# rapidshark-lipo-sensor-mk-3_1.net
KiCad netlist of a schematic drawn in EAGLE
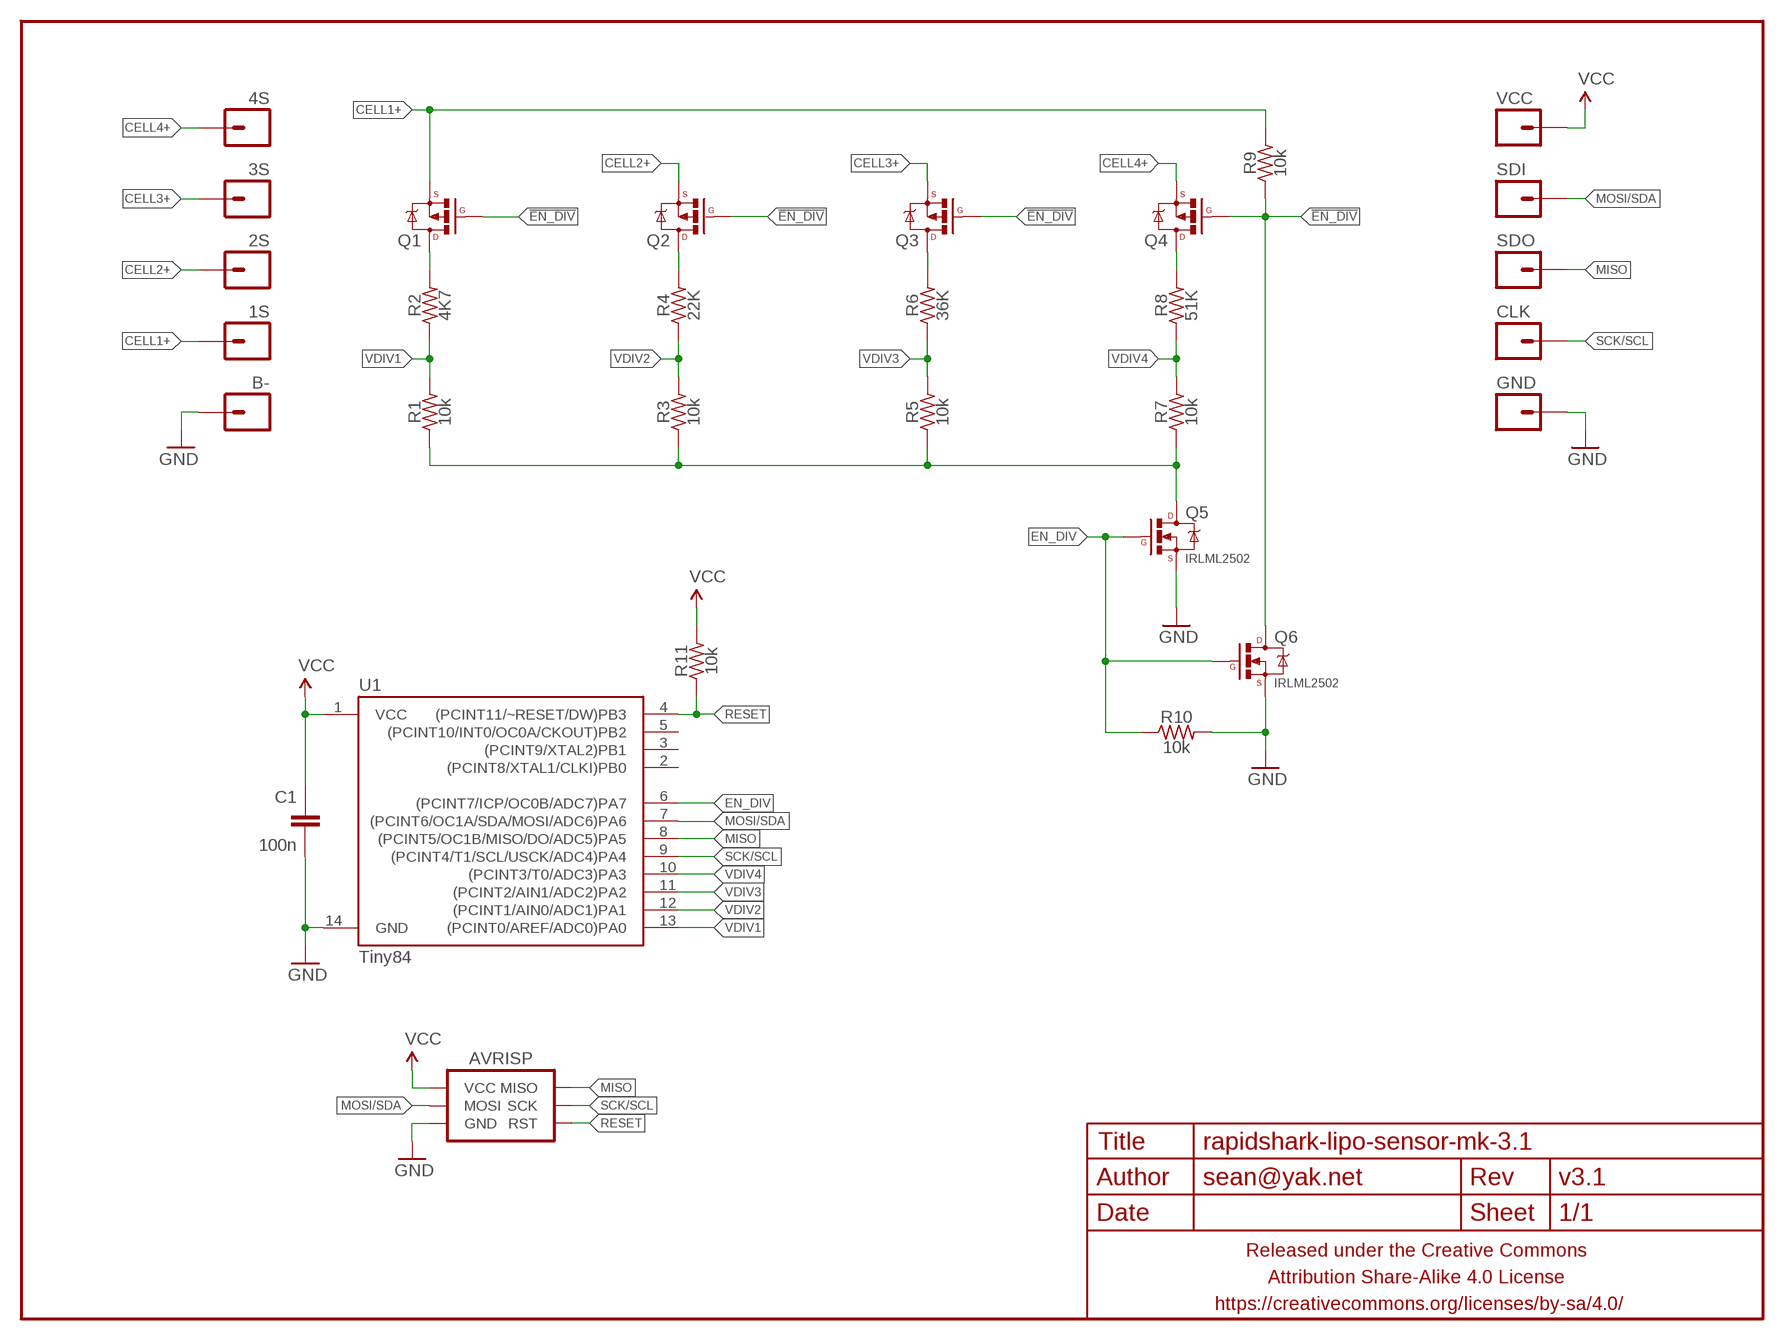
[diagram p0: schematic, sheet 1]

(export (version "E")
  (design (tool "Eeschema 10.0.6"))
  (components
    (comp (ref "1S")
      (value "M01PTH-0.9MM")
      (footprint "eagle-import:1X01-0.9MM")
      (libsource (lib "eagle-import") (part "M01PTH-0.9MM"))
    )
    (comp (ref "2S")
      (value "M01PTH-0.9MM")
      (footprint "eagle-import:1X01-0.9MM")
      (libsource (lib "eagle-import") (part "M01PTH-0.9MM"))
    )
    (comp (ref "3S")
      (value "M01PTH-0.9MM")
      (footprint "eagle-import:1X01-0.9MM")
      (libsource (lib "eagle-import") (part "M01PTH-0.9MM"))
    )
    (comp (ref "4S")
      (value "M01PTH-0.9MM")
      (footprint "eagle-import:1X01-0.9MM")
      (libsource (lib "eagle-import") (part "M01PTH-0.9MM"))
    )
    (comp (ref "AVRISP")
      (value "AVR_SPI_PRG_6SMD_TEST_POINTS")
      (footprint "eagle-import:2X3_SMD_TEST_POINTS")
      (libsource (lib "eagle-import") (part "AVR_SPI_PRG_6SMD_TEST_POINTS"))
    )
    (comp (ref "B-")
      (value "M01PTH-0.9MM")
      (footprint "eagle-import:1X01-0.9MM")
      (libsource (lib "eagle-import") (part "M01PTH-0.9MM"))
    )
    (comp (ref "C1")
      (value "100n")
      (footprint "eagle-import:C0603-TIGHTER")
      (libsource (lib "eagle-import") (part "CAPACITOR-CERAMICC0603-TIGHTER"))
    )
    (comp (ref "CLK")
      (value "M01PTH-0.9MM")
      (footprint "eagle-import:1X01-0.9MM")
      (libsource (lib "eagle-import") (part "M01PTH-0.9MM"))
    )
    (comp (ref "FRAME1")
      (value "FRAME-LETTERNO_PACKAGE")
      (footprint "eagle-import:DUMMY")
      (fields (field (name "DESIGNER") "sean@yak.net") (field (name "VERSION") "v3.1"))
      (libsource (lib "eagle-import") (part "FRAME-LETTERNO_PACKAGE"))
    )
    (comp (ref "GND")
      (value "M01PTH-0.9MM")
      (footprint "eagle-import:1X01-0.9MM")
      (libsource (lib "eagle-import") (part "M01PTH-0.9MM"))
    )
    (comp (ref "Q1")
      (value "MOSFET-PCHANNELSOT-23")
      (footprint "eagle-import:SOT23")
      (libsource (lib "eagle-import") (part "MOSFET-PCHANNELSOT-23"))
    )
    (comp (ref "Q2")
      (value "MOSFET-PCHANNELSOT-23")
      (footprint "eagle-import:SOT23")
      (libsource (lib "eagle-import") (part "MOSFET-PCHANNELSOT-23"))
    )
    (comp (ref "Q3")
      (value "MOSFET-PCHANNELSOT-23")
      (footprint "eagle-import:SOT23")
      (libsource (lib "eagle-import") (part "MOSFET-PCHANNELSOT-23"))
    )
    (comp (ref "Q4")
      (value "MOSFET-PCHANNELSOT-23")
      (footprint "eagle-import:SOT23")
      (libsource (lib "eagle-import") (part "MOSFET-PCHANNELSOT-23"))
    )
    (comp (ref "Q5")
      (value "IRLML2502")
      (footprint "eagle-import:SOT23")
      (libsource (lib "eagle-import") (part "MOSFET-NCHANNELIRLML2502"))
    )
    (comp (ref "Q6")
      (value "IRLML2502")
      (footprint "eagle-import:SOT23")
      (libsource (lib "eagle-import") (part "MOSFET-NCHANNELIRLML2502"))
    )
    (comp (ref "R1")
      (value "10k")
      (footprint "eagle-import:R0603-TIGHTER")
      (libsource (lib "eagle-import") (part "RESISTORR0603-TIGHTER"))
    )
    (comp (ref "R2")
      (value "4K7")
      (footprint "eagle-import:R0603-TIGHTER")
      (libsource (lib "eagle-import") (part "RESISTORR0603-TIGHTER"))
    )
    (comp (ref "R3")
      (value "10k")
      (footprint "eagle-import:R0603-TIGHTER")
      (libsource (lib "eagle-import") (part "RESISTORR0603-TIGHTER"))
    )
    (comp (ref "R4")
      (value "22K")
      (footprint "eagle-import:R0603-TIGHTER")
      (libsource (lib "eagle-import") (part "RESISTORR0603-TIGHTER"))
    )
    (comp (ref "R5")
      (value "10k")
      (footprint "eagle-import:R0603-TIGHTER")
      (libsource (lib "eagle-import") (part "RESISTORR0603-TIGHTER"))
    )
    (comp (ref "R6")
      (value "36K")
      (footprint "eagle-import:R0603-TIGHTER")
      (libsource (lib "eagle-import") (part "RESISTORR0603-TIGHTER"))
    )
    (comp (ref "R7")
      (value "10k")
      (footprint "eagle-import:R0603-TIGHTER")
      (libsource (lib "eagle-import") (part "RESISTORR0603-TIGHTER"))
    )
    (comp (ref "R8")
      (value "51K")
      (footprint "eagle-import:R0603-TIGHTER")
      (libsource (lib "eagle-import") (part "RESISTORR0603-TIGHTER"))
    )
    (comp (ref "R9")
      (value "10k")
      (footprint "eagle-import:R0603-TIGHTER")
      (libsource (lib "eagle-import") (part "RESISTORR0603-TIGHTER"))
    )
    (comp (ref "R10")
      (value "10k")
      (footprint "eagle-import:R0603-TIGHTER")
      (libsource (lib "eagle-import") (part "RESISTORR0603-TIGHTER"))
    )
    (comp (ref "R11")
      (value "10k")
      (footprint "eagle-import:R0603-TIGHTER")
      (libsource (lib "eagle-import") (part "RESISTORR0603-TIGHTER"))
    )
    (comp (ref "SDI")
      (value "M01PTH-0.9MM")
      (footprint "eagle-import:1X01-0.9MM")
      (libsource (lib "eagle-import") (part "M01PTH-0.9MM"))
    )
    (comp (ref "SDO")
      (value "M01PTH-0.9MM")
      (footprint "eagle-import:1X01-0.9MM")
      (libsource (lib "eagle-import") (part "M01PTH-0.9MM"))
    )
    (comp (ref "U1")
      (value "Tiny84")
      (footprint "eagle-import:SO14")
      (libsource (lib "eagle-import") (part "ATTINY84"))
    )
    (comp (ref "VCC")
      (value "M01PTH-0.9MM")
      (footprint "eagle-import:1X01-0.9MM")
      (libsource (lib "eagle-import") (part "M01PTH-0.9MM"))
    )
  )
  (nets
    (net (code "1") (name "/~{EN_DIV}") (class "Default")
      (node (ref "Q1") (pin "1") (pinfunction "G_1") (pintype "passive"))
      (node (ref "Q2") (pin "1") (pinfunction "G_1") (pintype "passive"))
      (node (ref "Q3") (pin "1") (pinfunction "G_1") (pintype "passive"))
      (node (ref "Q4") (pin "1") (pinfunction "G_1") (pintype "passive"))
      (node (ref "Q6") (pin "3") (pinfunction "D_3") (pintype "passive"))
      (node (ref "R9") (pin "1") (pinfunction "1_1") (pintype "passive"))
    )
    (net (code "2") (name "CELL1+") (class "Default")
      (node (ref "1S") (pin "1") (pinfunction "1_1") (pintype "passive"))
      (node (ref "Q1") (pin "2") (pinfunction "S_2") (pintype "passive"))
      (node (ref "R9") (pin "2") (pinfunction "2_2") (pintype "passive"))
    )
    (net (code "3") (name "CELL2+") (class "Default")
      (node (ref "2S") (pin "1") (pinfunction "1_1") (pintype "passive"))
      (node (ref "Q2") (pin "2") (pinfunction "S_2") (pintype "passive"))
    )
    (net (code "4") (name "CELL3+") (class "Default")
      (node (ref "3S") (pin "1") (pinfunction "1_1") (pintype "passive"))
      (node (ref "Q3") (pin "2") (pinfunction "S_2") (pintype "passive"))
    )
    (net (code "5") (name "CELL4+") (class "Default")
      (node (ref "4S") (pin "1") (pinfunction "1_1") (pintype "passive"))
      (node (ref "Q4") (pin "2") (pinfunction "S_2") (pintype "passive"))
    )
    (net (code "6") (name "EN_DIV") (class "Default")
      (node (ref "Q5") (pin "1") (pinfunction "G_1") (pintype "passive"))
      (node (ref "Q6") (pin "1") (pinfunction "G_1") (pintype "passive"))
      (node (ref "R10") (pin "1") (pinfunction "1_1") (pintype "passive"))
      (node (ref "U1") (pin "6") (pinfunction "(PCINT7/ICP/OC0B/ADC7)PA7_6") (pintype "bidirectional"))
    )
    (net (code "7") (name "GND") (class "Default")
      (node (ref "AVRISP") (pin "6") (pinfunction "GND_6") (pintype "passive"))
      (node (ref "B-") (pin "1") (pinfunction "1_1") (pintype "passive"))
      (node (ref "C1") (pin "2") (pinfunction "2_2") (pintype "passive"))
      (node (ref "GND") (pin "1") (pinfunction "1_1") (pintype "passive"))
      (node (ref "Q5") (pin "2") (pinfunction "S_2") (pintype "passive"))
      (node (ref "Q6") (pin "2") (pinfunction "S_2") (pintype "passive"))
      (node (ref "R10") (pin "2") (pinfunction "2_2") (pintype "passive"))
      (node (ref "U1") (pin "14") (pinfunction "GND_14") (pintype "bidirectional"))
    )
    (net (code "8") (name "MISO") (class "Default")
      (node (ref "AVRISP") (pin "1") (pinfunction "MISO_1") (pintype "passive"))
      (node (ref "SDO") (pin "1") (pinfunction "1_1") (pintype "passive"))
      (node (ref "U1") (pin "8") (pinfunction "(PCINT5/OC1B/MISO/DO/ADC5)PA5_8") (pintype "bidirectional"))
    )
    (net (code "9") (name "MOSI{slash}SDA") (class "Default")
      (node (ref "AVRISP") (pin "4") (pinfunction "MOSI_4") (pintype "passive"))
      (node (ref "SDI") (pin "1") (pinfunction "1_1") (pintype "passive"))
      (node (ref "U1") (pin "7") (pinfunction "(PCINT6/OC1A/SDA/MOSI/ADC6)PA6_7") (pintype "bidirectional"))
    )
    (net (code "10") (name "Net-(Q1-D)") (class "Default")
      (node (ref "Q1") (pin "3") (pinfunction "D_3") (pintype "passive"))
      (node (ref "R2") (pin "2") (pinfunction "2_2") (pintype "passive"))
    )
    (net (code "11") (name "Net-(Q2-D)") (class "Default")
      (node (ref "Q2") (pin "3") (pinfunction "D_3") (pintype "passive"))
      (node (ref "R4") (pin "2") (pinfunction "2_2") (pintype "passive"))
    )
    (net (code "12") (name "Net-(Q3-D)") (class "Default")
      (node (ref "Q3") (pin "3") (pinfunction "D_3") (pintype "passive"))
      (node (ref "R6") (pin "2") (pinfunction "2_2") (pintype "passive"))
    )
    (net (code "13") (name "Net-(Q4-D)") (class "Default")
      (node (ref "Q4") (pin "3") (pinfunction "D_3") (pintype "passive"))
      (node (ref "R8") (pin "2") (pinfunction "2_2") (pintype "passive"))
    )
    (net (code "14") (name "Net-(Q5-D)") (class "Default")
      (node (ref "Q5") (pin "3") (pinfunction "D_3") (pintype "passive"))
      (node (ref "R1") (pin "1") (pinfunction "1_1") (pintype "passive"))
      (node (ref "R3") (pin "1") (pinfunction "1_1") (pintype "passive"))
      (node (ref "R5") (pin "1") (pinfunction "1_1") (pintype "passive"))
      (node (ref "R7") (pin "1") (pinfunction "1_1") (pintype "passive"))
    )
    (net (code "15") (name "RESET") (class "Default")
      (node (ref "AVRISP") (pin "5") (pinfunction "RST_5") (pintype "passive"))
      (node (ref "R11") (pin "1") (pinfunction "1_1") (pintype "passive"))
      (node (ref "U1") (pin "4") (pinfunction "(PCINT11/~{RESET/DW})PB3_4") (pintype "bidirectional"))
    )
    (net (code "16") (name "SCK{slash}SCL") (class "Default")
      (node (ref "AVRISP") (pin "3") (pinfunction "SCK_3") (pintype "passive"))
      (node (ref "CLK") (pin "1") (pinfunction "1_1") (pintype "passive"))
      (node (ref "U1") (pin "9") (pinfunction "(PCINT4/T1/SCL/USCK/ADC4)PA4_9") (pintype "bidirectional"))
    )
    (net (code "17") (name "VCC") (class "Default")
      (node (ref "AVRISP") (pin "2") (pinfunction "VCC_2") (pintype "passive"))
      (node (ref "C1") (pin "1") (pinfunction "1_1") (pintype "passive"))
      (node (ref "R11") (pin "2") (pinfunction "2_2") (pintype "passive"))
      (node (ref "U1") (pin "1") (pinfunction "VCC_1") (pintype "bidirectional"))
      (node (ref "VCC") (pin "1") (pinfunction "1_1") (pintype "passive"))
    )
    (net (code "18") (name "VDIV1") (class "Default")
      (node (ref "R1") (pin "2") (pinfunction "2_2") (pintype "passive"))
      (node (ref "R2") (pin "1") (pinfunction "1_1") (pintype "passive"))
      (node (ref "U1") (pin "13") (pinfunction "(PCINT0/AREF/ADC0)PA0_13") (pintype "bidirectional"))
    )
    (net (code "19") (name "VDIV2") (class "Default")
      (node (ref "R3") (pin "2") (pinfunction "2_2") (pintype "passive"))
      (node (ref "R4") (pin "1") (pinfunction "1_1") (pintype "passive"))
      (node (ref "U1") (pin "12") (pinfunction "(PCINT1/AIN0/ADC1)PA1_12") (pintype "bidirectional"))
    )
    (net (code "20") (name "VDIV3") (class "Default")
      (node (ref "R5") (pin "2") (pinfunction "2_2") (pintype "passive"))
      (node (ref "R6") (pin "1") (pinfunction "1_1") (pintype "passive"))
      (node (ref "U1") (pin "11") (pinfunction "(PCINT2/AIN1/ADC2)PA2_11") (pintype "bidirectional"))
    )
    (net (code "21") (name "VDIV4") (class "Default")
      (node (ref "R7") (pin "2") (pinfunction "2_2") (pintype "passive"))
      (node (ref "R8") (pin "1") (pinfunction "1_1") (pintype "passive"))
      (node (ref "U1") (pin "10") (pinfunction "(PCINT3/T0/ADC3)PA3_10") (pintype "bidirectional"))
    )
    (net (code "22") (name "unconnected-(U1-(PCINT8{slash}XTAL1{slash}CLKI)PB0-Pad2)") (class "Default")
      (node (ref "U1") (pin "2") (pinfunction "(PCINT8/XTAL1/CLKI)PB0_2") (pintype "bidirectional"))
    )
    (net (code "23") (name "unconnected-(U1-(PCINT9{slash}XTAL2)PB1-Pad3)") (class "Default")
      (node (ref "U1") (pin "3") (pinfunction "(PCINT9/XTAL2)PB1_3") (pintype "bidirectional"))
    )
    (net (code "24") (name "unconnected-(U1-(PCINT10{slash}INT0{slash}OC0A{slash}CKOUT)PB2-Pad5)") (class "Default")
      (node (ref "U1") (pin "5") (pinfunction "(PCINT10/INT0/OC0A/CKOUT)PB2_5") (pintype "bidirectional"))
    )
  )
)
